# GyroBoard.net
KiCad netlist of a schematic drawn in Altium Designer
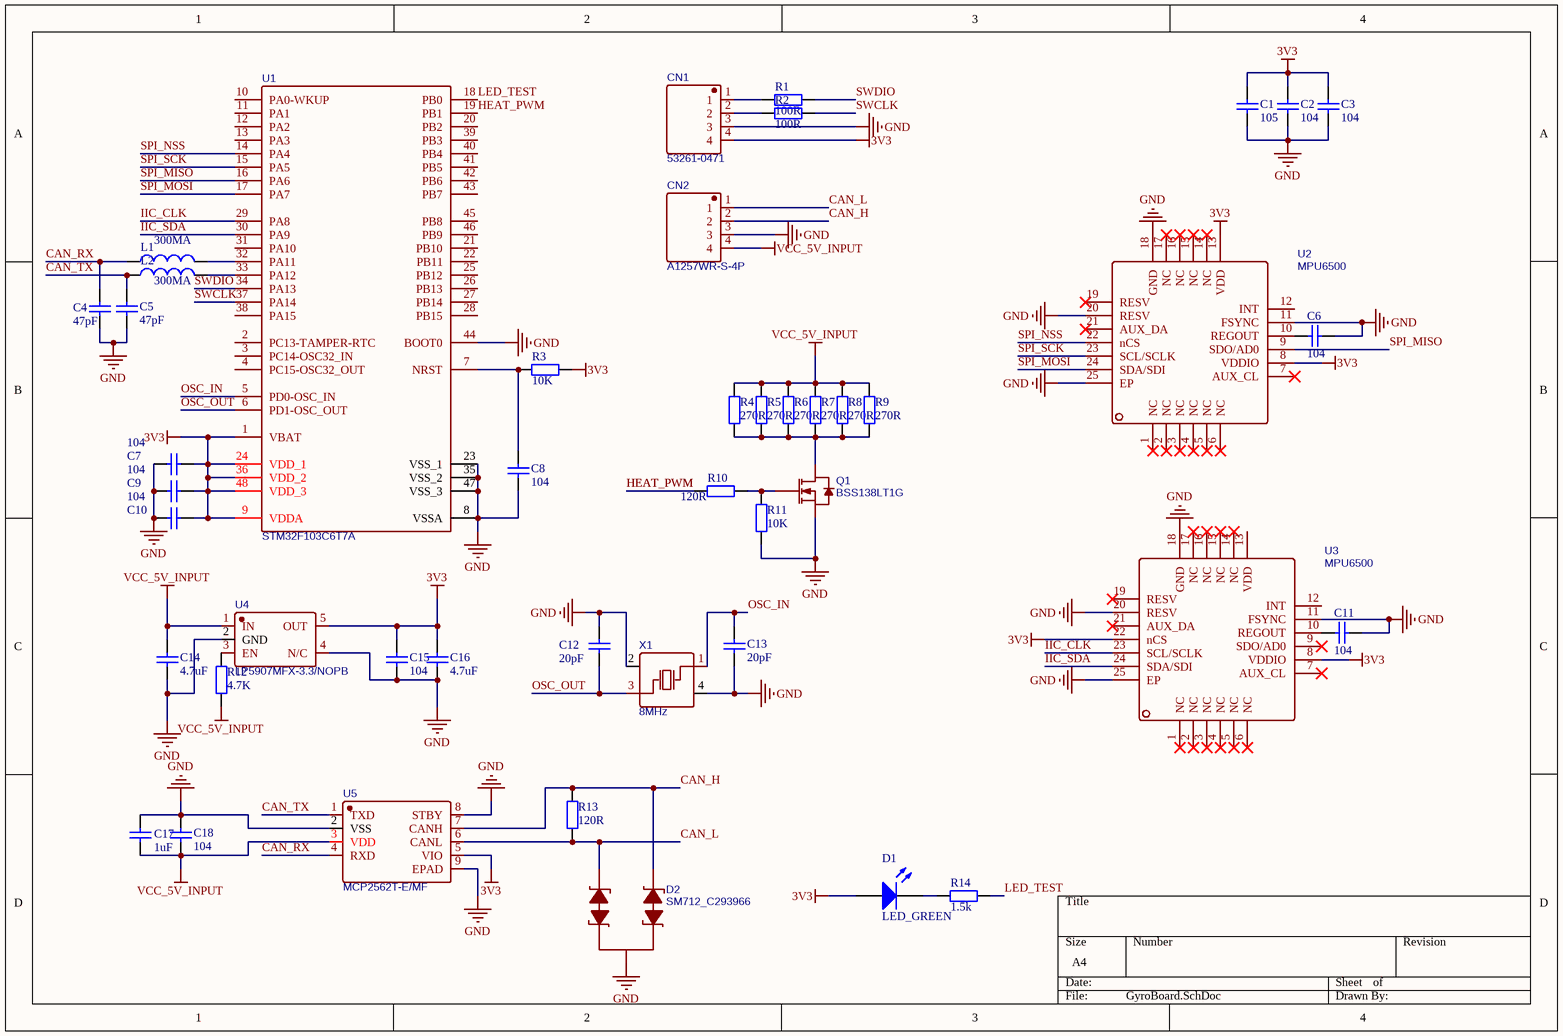
[diagram p0: GyroBoard.SchDoc]

(export (version "E")
  (design (tool "Eeschema 10.0.6"))
  (components
    (comp (ref "C1")
      (value "105")
      (footprint "0402")
      (description "Capacitor")
      (fields (field (name "PUBLISHER") "Altium Limited"))
      (libsource (lib "STM32 3.0") (part "Cap"))
    )
    (comp (ref "C2")
      (value "104")
      (footprint "0402")
      (description "Capacitor")
      (fields (field (name "PUBLISHER") "Altium Limited"))
      (libsource (lib "STM32 3.0") (part "Cap"))
    )
    (comp (ref "C3")
      (value "104")
      (footprint "0402")
      (description "Capacitor")
      (fields (field (name "PUBLISHER") "Altium Limited"))
      (libsource (lib "STM32 3.0") (part "Cap"))
    )
    (comp (ref "C4")
      (value "47pF")
      (footprint "0402")
      (description "Capacitor")
      (fields (field (name "PUBLISHER") "Altium Limited"))
      (libsource (lib "STM32 3.0") (part "Cap"))
    )
    (comp (ref "C5")
      (value "47pF")
      (footprint "0402")
      (description "Capacitor")
      (fields (field (name "PUBLISHER") "Altium Limited"))
      (libsource (lib "STM32 3.0") (part "Cap"))
    )
    (comp (ref "C6")
      (value "104")
      (footprint "0402")
      (description "Capacitor")
      (fields (field (name "PUBLISHER") "Altium Limited"))
      (libsource (lib "STM32 3.0") (part "Cap"))
    )
    (comp (ref "C7")
      (value "104")
      (footprint "0402")
      (description "Capacitor")
      (fields (field (name "PUBLISHER") "Altium Limited"))
      (libsource (lib "STM32 3.0") (part "Cap"))
    )
    (comp (ref "C8")
      (value "104")
      (footprint "0402")
      (description "Capacitor")
      (fields (field (name "PUBLISHER") "Altium Limited"))
      (libsource (lib "STM32 3.0") (part "Cap"))
    )
    (comp (ref "C9")
      (value "104")
      (footprint "0402")
      (description "Capacitor")
      (fields (field (name "PUBLISHER") "Altium Limited"))
      (libsource (lib "STM32 3.0") (part "Cap"))
    )
    (comp (ref "C10")
      (value "104")
      (footprint "0402")
      (description "Capacitor")
      (fields (field (name "PUBLISHER") "Altium Limited"))
      (libsource (lib "STM32 3.0") (part "Cap"))
    )
    (comp (ref "C11")
      (value "104")
      (footprint "0402")
      (description "Capacitor")
      (fields (field (name "PUBLISHER") "Altium Limited"))
      (libsource (lib "STM32 3.0") (part "Cap"))
    )
    (comp (ref "C12")
      (value "20pF")
      (footprint "0402")
      (description "Capacitor")
      (fields (field (name "PUBLISHER") "Altium Limited"))
      (libsource (lib "STM32 3.0") (part "Cap"))
    )
    (comp (ref "C13")
      (value "20pF")
      (footprint "0402")
      (description "Capacitor")
      (fields (field (name "PUBLISHER") "Altium Limited"))
      (libsource (lib "STM32 3.0") (part "Cap"))
    )
    (comp (ref "C14")
      (value "4.7uF")
      (footprint "0402")
      (description "Capacitor")
      (fields (field (name "PUBLISHER") "Altium Limited"))
      (libsource (lib "STM32 3.0") (part "Cap"))
    )
    (comp (ref "C15")
      (value "104")
      (footprint "0402")
      (description "Capacitor")
      (fields (field (name "PUBLISHER") "Altium Limited"))
      (libsource (lib "STM32 3.0") (part "Cap"))
    )
    (comp (ref "C16")
      (value "4.7uF")
      (footprint "CAP-CASE-A_3216")
      (description "Capacitor")
      (fields (field (name "PUBLISHER") "Altium Limited"))
      (libsource (lib "STM32 3.0") (part "Cap"))
    )
    (comp (ref "C17")
      (value "1uF")
      (footprint "0402")
      (description "Capacitor")
      (fields (field (name "PUBLISHER") "Altium Limited"))
      (libsource (lib "STM32 3.0") (part "Cap"))
    )
    (comp (ref "C18")
      (value "104")
      (footprint "0402")
      (description "Capacitor")
      (fields (field (name "PUBLISHER") "Altium Limited"))
      (libsource (lib "STM32 3.0") (part "Cap"))
    )
    (comp (ref "CN1")
      (value "53261-0471")
      (footprint "532610471")
      (fields
        (field (name "BOM_SUPPLIER PART") "C240848")
        (field (name "BOM_MANUFACTURER PART") "53261-0871")
        (field (name "CONTRIBUTOR") "LCSC")
      )
      (libsource (lib "GyroBoard") (part "53261-0471"))
    )
    (comp (ref "CN2")
      (value "A1257WR-S-4P")
      (footprint "A1257WR-S-4P")
      (fields
        (field (name "BOM_SUPPLIER PART") "C240848")
        (field (name "BOM_MANUFACTURER PART") "53261-0871")
        (field (name "CONTRIBUTOR") "LCSC")
      )
      (libsource (lib "GyroBoard") (part "A1257WV-S-4P"))
    )
    (comp (ref "D1")
      (value "LED_GREEN")
      (footprint "GyroBoard:LED-0603")
      (description "Typical INFRARED GaAs LED")
      (fields (field (name "PUBLISHER") "Altium Limited"))
      (libsource (lib "Miscellaneous Devices") (part "LED0"))
    )
    (comp (ref "D2")
      (value "SM712_C293966")
      (footprint "SOT-23-3")
      (fields
        (field (name "BOM_SUPPLIER PART") "C293966")
        (field (name "BOM_MANUFACTURER PART") "SM712")
        (field (name "CONTRIBUTOR") "LCSC")
      )
      (libsource (lib "GyroBoard") (part "SM712_C293966"))
    )
    (comp (ref "L1")
      (value "300MA")
      (footprint "GyroBoard:0402")
      (description "CBG100505U310T")
      (fields (field (name "PUBLISHER") "Altium Limited"))
      (libsource (lib "Miscellaneous Devices") (part "Inductor"))
    )
    (comp (ref "L2")
      (value "300MA")
      (footprint "GyroBoard:0402")
      (description "CBG100505U310T")
      (fields (field (name "PUBLISHER") "Altium Limited"))
      (libsource (lib "Miscellaneous Devices") (part "Inductor"))
    )
    (comp (ref "Q1")
      (value "BSS138LT1G")
      (footprint "SOT-23(SOT-23-3)")
      (fields (field (name "BOM_SUPPLIER PART") "C82045"))
      (libsource (lib "GyroBoard") (part "BSS138LT1G"))
    )
    (comp (ref "R1")
      (value "100R")
      (footprint "0402")
      (description "Resistor")
      (fields (field (name "PUBLISHER") "Altium Limited"))
      (libsource (lib "") (part "Res2_2"))
    )
    (comp (ref "R2")
      (value "100R")
      (footprint "0402")
      (description "Resistor")
      (fields (field (name "PUBLISHER") "Altium Limited"))
      (libsource (lib "") (part "Res2_2"))
    )
    (comp (ref "R3")
      (value "10K")
      (footprint "0402")
      (description "Resistor")
      (fields (field (name "PUBLISHER") "Altium Limited"))
      (libsource (lib "") (part "Res2_3"))
    )
    (comp (ref "R4")
      (value "270R")
      (footprint "0402")
      (description "Resistor")
      (fields (field (name "PUBLISHER") "Altium Limited"))
      (libsource (lib "") (part "Res2_1"))
    )
    (comp (ref "R5")
      (value "270R")
      (footprint "0402")
      (description "Resistor")
      (fields (field (name "PUBLISHER") "Altium Limited"))
      (libsource (lib "") (part "Res2_1"))
    )
    (comp (ref "R6")
      (value "270R")
      (footprint "0402")
      (description "Resistor")
      (fields (field (name "PUBLISHER") "Altium Limited"))
      (libsource (lib "") (part "Res2_1"))
    )
    (comp (ref "R7")
      (value "270R")
      (footprint "0402")
      (description "Resistor")
      (fields (field (name "PUBLISHER") "Altium Limited"))
      (libsource (lib "") (part "Res2_1"))
    )
    (comp (ref "R8")
      (value "270R")
      (footprint "0402")
      (description "Resistor")
      (fields (field (name "PUBLISHER") "Altium Limited"))
      (libsource (lib "") (part "Res2_1"))
    )
    (comp (ref "R9")
      (value "270R")
      (footprint "0402")
      (description "Resistor")
      (fields (field (name "PUBLISHER") "Altium Limited"))
      (libsource (lib "") (part "Res2_1"))
    )
    (comp (ref "R10")
      (value "120R")
      (footprint "0402")
      (description "Resistor")
      (fields (field (name "PUBLISHER") "Altium Limited"))
      (libsource (lib "") (part "Res2_2"))
    )
    (comp (ref "R11")
      (value "10K")
      (footprint "0402")
      (description "Resistor")
      (fields (field (name "PUBLISHER") "Altium Limited"))
      (libsource (lib "STM32 3.0") (part "Res2"))
    )
    (comp (ref "R12")
      (value "4.7K")
      (footprint "0402")
      (description "Resistor")
      (fields (field (name "PUBLISHER") "Altium Limited"))
      (libsource (lib "STM32 3.0") (part "Res2"))
    )
    (comp (ref "R13")
      (value "120R")
      (footprint "0402")
      (description "Resistor")
      (fields (field (name "PUBLISHER") "Altium Limited"))
      (libsource (lib "STM32 3.0") (part "Res2"))
    )
    (comp (ref "R14")
      (value "1.5k")
      (footprint "0402")
      (description "Resistor")
      (fields (field (name "PUBLISHER") "Altium Limited"))
      (libsource (lib "") (part "Res2_2"))
    )
    (comp (ref "U1")
      (value "STM32F103C6T7A")
      (footprint "QFP-48_LSA9.2-LSB9.2-H1.6-PITCH0.5-TL")
      (fields (field (name "BOM_SUPPLIER PART") "C222074") (field (name "CONTRIBUTOR") "LCSC"))
      (libsource (lib "GyroBoard") (part "STM32F103C6T7A"))
    )
    (comp (ref "U2")
      (value "MPU6500")
      (footprint "QFN24-EP")
      (fields (field (name "BOM_SUPPLIER PART") "C50278"))
      (libsource (lib "GyroBoard") (part "MPU6500_1"))
    )
    (comp (ref "U3")
      (value "MPU6500")
      (footprint "QFN24-EP")
      (fields (field (name "BOM_SUPPLIER PART") "C50278"))
      (libsource (lib "GyroBoard") (part "MPU6500_1"))
    )
    (comp (ref "U4")
      (value "LP5907MFX-3.3/NOPB")
      (footprint "SOT-23-5")
      (fields (field (name "BOM_SUPPLIER PART") "C80670") (field (name "CONTRIBUTOR") "LCSC"))
      (libsource (lib "GyroBoard") (part "LP5907MFX-3.3/NOPB"))
    )
    (comp (ref "U5")
      (value "MCP2562T-E/MF")
      (footprint "DFN-8_EP_3X3MM")
      (fields (field (name "BOM_SUPPLIER PART") "C191416") (field (name "CONTRIBUTOR") "LCSC"))
      (libsource (lib "GyroBoard") (part "MCP2562T-E/MF"))
    )
    (comp (ref "X1")
      (value "8MHz")
      (footprint "SMD-5032_4P")
      (fields
        (field (name "BOM_MANUFACTURER PART") "SMD-5032_4P8M20pf20ppm")
        (field (name "BOM_SUPPLIER PART") "C133333")
        (field (name "CONTRIBUTOR") "LCSC")
      )
      (libsource (lib "GyroBoard") (part "8MHz"))
    )
  )
  (nets
    (net (code "1") (name "/CAN_H") (class "Default")
      (node (ref "CN2") (pin "2") (pinfunction "2_2") (pintype "passive"))
      (node (ref "D2") (pin "1") (pinfunction "1_1") (pintype "passive"))
      (node (ref "R13") (pin "2") (pinfunction "2_2") (pintype "passive"))
      (node (ref "U5") (pin "7") (pinfunction "CANH_7") (pintype "passive"))
    )
    (net (code "2") (name "/CAN_L") (class "Default")
      (node (ref "CN2") (pin "1") (pinfunction "1_1") (pintype "passive"))
      (node (ref "D2") (pin "2") (pinfunction "2_2") (pintype "passive"))
      (node (ref "R13") (pin "1") (pinfunction "1_1") (pintype "passive"))
      (node (ref "U5") (pin "6") (pinfunction "CANL_6") (pintype "passive"))
    )
    (net (code "3") (name "/CAN_RX") (class "Default")
      (node (ref "C4") (pin "1") (pinfunction "1_1") (pintype "passive"))
      (node (ref "L1") (pin "1") (pinfunction "1_1") (pintype "passive"))
      (node (ref "U5") (pin "4") (pinfunction "RXD_4") (pintype "passive"))
    )
    (net (code "4") (name "/CAN_TX") (class "Default")
      (node (ref "C5") (pin "1") (pinfunction "1_1") (pintype "passive"))
      (node (ref "L2") (pin "1") (pinfunction "1_1") (pintype "passive"))
      (node (ref "U5") (pin "1") (pinfunction "TXD_1") (pintype "passive"))
    )
    (net (code "5") (name "/HEAT_PWM") (class "Default")
      (node (ref "R10") (pin "2") (pinfunction "2_2") (pintype "passive"))
      (node (ref "U1") (pin "19") (pinfunction "PB1_19") (pintype "passive"))
    )
    (net (code "6") (name "/IIC_CLK") (class "Default")
      (node (ref "U1") (pin "29") (pinfunction "PA8_29") (pintype "passive"))
      (node (ref "U3") (pin "23") (pinfunction "SCL/SCLK_23") (pintype "passive"))
    )
    (net (code "7") (name "/IIC_SDA") (class "Default")
      (node (ref "U1") (pin "30") (pinfunction "PA9_30") (pintype "passive"))
      (node (ref "U3") (pin "24") (pinfunction "SDA/SDI_24") (pintype "passive"))
    )
    (net (code "8") (name "/LED_TEST") (class "Default")
      (node (ref "R14") (pin "1") (pinfunction "1_1") (pintype "passive"))
      (node (ref "U1") (pin "18") (pinfunction "PB0_18") (pintype "passive"))
    )
    (net (code "9") (name "/OSC_IN") (class "Default")
      (node (ref "C13") (pin "1") (pinfunction "1_1") (pintype "passive"))
      (node (ref "U1") (pin "5") (pinfunction "PD0-OSC_IN_5") (pintype "passive"))
      (node (ref "X1") (pin "1") (pinfunction "OSC1_1") (pintype "passive"))
    )
    (net (code "10") (name "/OSC_OUT") (class "Default")
      (node (ref "C12") (pin "2") (pinfunction "2_2") (pintype "passive"))
      (node (ref "U1") (pin "6") (pinfunction "PD1-OSC_OUT_6") (pintype "passive"))
      (node (ref "X1") (pin "3") (pinfunction "OSC2_3") (pintype "passive"))
    )
    (net (code "11") (name "/SPI_MISO") (class "Default")
      (node (ref "U1") (pin "16") (pinfunction "PA6_16") (pintype "passive"))
      (node (ref "U2") (pin "9") (pinfunction "SDO/AD0_9") (pintype "passive"))
    )
    (net (code "12") (name "/SPI_MOSI") (class "Default")
      (node (ref "U1") (pin "17") (pinfunction "PA7_17") (pintype "passive"))
      (node (ref "U2") (pin "24") (pinfunction "SDA/SDI_24") (pintype "passive"))
    )
    (net (code "13") (name "/SPI_NSS") (class "Default")
      (node (ref "U1") (pin "14") (pinfunction "PA4_14") (pintype "passive"))
      (node (ref "U2") (pin "22") (pinfunction "nCS_22") (pintype "passive"))
    )
    (net (code "14") (name "/SPI_SCK") (class "Default")
      (node (ref "U1") (pin "15") (pinfunction "PA5_15") (pintype "passive"))
      (node (ref "U2") (pin "23") (pinfunction "SCL/SCLK_23") (pintype "passive"))
    )
    (net (code "15") (name "/SWCLK") (class "Default")
      (node (ref "R2") (pin "1") (pinfunction "1_1") (pintype "passive"))
      (node (ref "U1") (pin "37") (pinfunction "PA14_37") (pintype "passive"))
    )
    (net (code "16") (name "/SWDIO") (class "Default")
      (node (ref "R1") (pin "1") (pinfunction "1_1") (pintype "passive"))
      (node (ref "U1") (pin "34") (pinfunction "PA13_34") (pintype "passive"))
    )
    (net (code "17") (name "3V3") (class "Default")
      (node (ref "C1") (pin "2") (pinfunction "2_2") (pintype "passive"))
      (node (ref "C10") (pin "1") (pinfunction "1_1") (pintype "passive"))
      (node (ref "C15") (pin "2") (pinfunction "2_2") (pintype "passive"))
      (node (ref "C16") (pin "2") (pinfunction "2_2") (pintype "passive"))
      (node (ref "C2") (pin "2") (pinfunction "2_2") (pintype "passive"))
      (node (ref "C3") (pin "1") (pinfunction "1_1") (pintype "passive"))
      (node (ref "C7") (pin "1") (pinfunction "1_1") (pintype "passive"))
      (node (ref "C9") (pin "1") (pinfunction "1_1") (pintype "passive"))
      (node (ref "CN1") (pin "4") (pinfunction "4_4") (pintype "passive"))
      (node (ref "D1") (pin "1") (pinfunction "A_1") (pintype "passive"))
      (node (ref "R3") (pin "2") (pinfunction "2_2") (pintype "passive"))
      (node (ref "U1") (pin "1") (pinfunction "VBAT_1") (pintype "passive"))
      (node (ref "U1") (pin "24") (pinfunction "VDD_1_24") (pintype "passive"))
      (node (ref "U1") (pin "36") (pinfunction "VDD_2_36") (pintype "passive"))
      (node (ref "U1") (pin "48") (pinfunction "VDD_3_48") (pintype "passive"))
      (node (ref "U1") (pin "9") (pinfunction "VDDA_9") (pintype "passive"))
      (node (ref "U2") (pin "13") (pinfunction "VDD_13") (pintype "passive"))
      (node (ref "U2") (pin "8") (pinfunction "VDDIO_8") (pintype "passive"))
      (node (ref "U3") (pin "22") (pinfunction "nCS_22") (pintype "passive"))
      (node (ref "U3") (pin "8") (pinfunction "VDDIO_8") (pintype "passive"))
      (node (ref "U4") (pin "5") (pinfunction "OUT_5") (pintype "passive"))
      (node (ref "U5") (pin "5") (pinfunction "VIO_5") (pintype "passive"))
    )
    (net (code "18") (name "GND") (class "Default")
      (node (ref "C1") (pin "1") (pinfunction "1_1") (pintype "passive"))
      (node (ref "C10") (pin "2") (pinfunction "2_2") (pintype "passive"))
      (node (ref "C11") (pin "2") (pinfunction "2_2") (pintype "passive"))
      (node (ref "C12") (pin "1") (pinfunction "1_1") (pintype "passive"))
      (node (ref "C13") (pin "2") (pinfunction "2_2") (pintype "passive"))
      (node (ref "C14") (pin "2") (pinfunction "2_2") (pintype "passive"))
      (node (ref "C15") (pin "1") (pinfunction "1_1") (pintype "passive"))
      (node (ref "C16") (pin "1") (pinfunction "1_1") (pintype "passive"))
      (node (ref "C17") (pin "1") (pinfunction "1_1") (pintype "passive"))
      (node (ref "C18") (pin "1") (pinfunction "1_1") (pintype "passive"))
      (node (ref "C2") (pin "1") (pinfunction "1_1") (pintype "passive"))
      (node (ref "C3") (pin "2") (pinfunction "2_2") (pintype "passive"))
      (node (ref "C4") (pin "2") (pinfunction "2_2") (pintype "passive"))
      (node (ref "C5") (pin "2") (pinfunction "2_2") (pintype "passive"))
      (node (ref "C6") (pin "2") (pinfunction "2_2") (pintype "passive"))
      (node (ref "C7") (pin "2") (pinfunction "2_2") (pintype "passive"))
      (node (ref "C8") (pin "1") (pinfunction "1_1") (pintype "passive"))
      (node (ref "C9") (pin "2") (pinfunction "2_2") (pintype "passive"))
      (node (ref "CN1") (pin "3") (pinfunction "3_3") (pintype "passive"))
      (node (ref "CN2") (pin "3") (pinfunction "3_3") (pintype "passive"))
      (node (ref "D2") (pin "3") (pinfunction "3_3") (pintype "passive"))
      (node (ref "Q1") (pin "2") (pinfunction "S_2") (pintype "passive"))
      (node (ref "R11") (pin "1") (pinfunction "1_1") (pintype "passive"))
      (node (ref "U1") (pin "23") (pinfunction "VSS_1_23") (pintype "passive"))
      (node (ref "U1") (pin "35") (pinfunction "VSS_2_35") (pintype "passive"))
      (node (ref "U1") (pin "44") (pinfunction "BOOT0_44") (pintype "passive"))
      (node (ref "U1") (pin "47") (pinfunction "VSS_3_47") (pintype "passive"))
      (node (ref "U1") (pin "8") (pinfunction "VSSA_8") (pintype "passive"))
      (node (ref "U2") (pin "11") (pinfunction "FSYNC_11") (pintype "passive"))
      (node (ref "U2") (pin "18") (pinfunction "GND_18") (pintype "passive"))
      (node (ref "U2") (pin "20") (pinfunction "RESV_20") (pintype "passive"))
      (node (ref "U2") (pin "25") (pinfunction "EP_25") (pintype "passive"))
      (node (ref "U3") (pin "11") (pinfunction "FSYNC_11") (pintype "passive"))
      (node (ref "U3") (pin "18") (pinfunction "GND_18") (pintype "passive"))
      (node (ref "U3") (pin "20") (pinfunction "RESV_20") (pintype "passive"))
      (node (ref "U3") (pin "25") (pinfunction "EP_25") (pintype "passive"))
      (node (ref "U4") (pin "2") (pinfunction "GND_2") (pintype "passive"))
      (node (ref "U4") (pin "4") (pinfunction "N/C_4") (pintype "passive"))
      (node (ref "U5") (pin "2") (pinfunction "VSS_2") (pintype "passive"))
      (node (ref "U5") (pin "8") (pinfunction "STBY_8") (pintype "passive"))
      (node (ref "U5") (pin "9") (pinfunction "EPAD_9") (pintype "passive"))
      (node (ref "X1") (pin "2") (pinfunction "GND_2") (pintype "passive"))
      (node (ref "X1") (pin "4") (pinfunction "GND_4") (pintype "passive"))
    )
    (net (code "19") (name "Net-(CN1-Pad1)") (class "Default")
      (node (ref "CN1") (pin "1") (pinfunction "1_1") (pintype "passive"))
      (node (ref "R1") (pin "2") (pinfunction "2_2") (pintype "passive"))
    )
    (net (code "20") (name "Net-(CN1-Pad2)") (class "Default")
      (node (ref "CN1") (pin "2") (pinfunction "2_2") (pintype "passive"))
      (node (ref "R2") (pin "2") (pinfunction "2_2") (pintype "passive"))
    )
    (net (code "21") (name "Net-(D1-K)") (class "Default")
      (node (ref "D1") (pin "2") (pinfunction "K_2") (pintype "passive"))
      (node (ref "R14") (pin "2") (pinfunction "2_2") (pintype "passive"))
    )
    (net (code "22") (name "Net-(Q1-D)") (class "Default")
      (node (ref "Q1") (pin "3") (pinfunction "D_3") (pintype "passive"))
      (node (ref "R4") (pin "2") (pinfunction "2_2") (pintype "passive"))
      (node (ref "R5") (pin "2") (pinfunction "2_2") (pintype "passive"))
      (node (ref "R6") (pin "2") (pinfunction "2_2") (pintype "passive"))
      (node (ref "R7") (pin "2") (pinfunction "2_2") (pintype "passive"))
      (node (ref "R8") (pin "2") (pinfunction "2_2") (pintype "passive"))
      (node (ref "R9") (pin "2") (pinfunction "2_2") (pintype "passive"))
    )
    (net (code "23") (name "Net-(Q1-G)") (class "Default")
      (node (ref "Q1") (pin "1") (pinfunction "G_1") (pintype "passive"))
      (node (ref "R10") (pin "1") (pinfunction "1_1") (pintype "passive"))
      (node (ref "R11") (pin "2") (pinfunction "2_2") (pintype "passive"))
    )
    (net (code "24") (name "Net-(U1-NRST)") (class "Default")
      (node (ref "C8") (pin "2") (pinfunction "2_2") (pintype "passive"))
      (node (ref "R3") (pin "1") (pinfunction "1_1") (pintype "passive"))
      (node (ref "U1") (pin "7") (pinfunction "NRST_7") (pintype "passive"))
    )
    (net (code "25") (name "Net-(U1-PA11)") (class "Default")
      (node (ref "L1") (pin "2") (pinfunction "2_2") (pintype "passive"))
      (node (ref "U1") (pin "32") (pinfunction "PA11_32") (pintype "passive"))
    )
    (net (code "26") (name "Net-(U1-PA12)") (class "Default")
      (node (ref "L2") (pin "2") (pinfunction "2_2") (pintype "passive"))
      (node (ref "U1") (pin "33") (pinfunction "PA12_33") (pintype "passive"))
    )
    (net (code "27") (name "Net-(U2-REGOUT)") (class "Default")
      (node (ref "C6") (pin "1") (pinfunction "1_1") (pintype "passive"))
      (node (ref "U2") (pin "10") (pinfunction "REGOUT_10") (pintype "passive"))
    )
    (net (code "28") (name "Net-(U3-REGOUT)") (class "Default")
      (node (ref "C11") (pin "1") (pinfunction "1_1") (pintype "passive"))
      (node (ref "U3") (pin "10") (pinfunction "REGOUT_10") (pintype "passive"))
    )
    (net (code "29") (name "Net-(U4-EN)") (class "Default")
      (node (ref "R12") (pin "2") (pinfunction "2_2") (pintype "passive"))
      (node (ref "U4") (pin "3") (pinfunction "EN_3") (pintype "passive"))
    )
    (net (code "30") (name "VCC_5V_INPUT") (class "Default")
      (node (ref "C14") (pin "1") (pinfunction "1_1") (pintype "passive"))
      (node (ref "C17") (pin "2") (pinfunction "2_2") (pintype "passive"))
      (node (ref "C18") (pin "2") (pinfunction "2_2") (pintype "passive"))
      (node (ref "CN2") (pin "4") (pinfunction "4_4") (pintype "passive"))
      (node (ref "R12") (pin "1") (pinfunction "1_1") (pintype "passive"))
      (node (ref "R4") (pin "1") (pinfunction "1_1") (pintype "passive"))
      (node (ref "R5") (pin "1") (pinfunction "1_1") (pintype "passive"))
      (node (ref "R6") (pin "1") (pinfunction "1_1") (pintype "passive"))
      (node (ref "R7") (pin "1") (pinfunction "1_1") (pintype "passive"))
      (node (ref "R8") (pin "1") (pinfunction "1_1") (pintype "passive"))
      (node (ref "R9") (pin "1") (pinfunction "1_1") (pintype "passive"))
      (node (ref "U4") (pin "1") (pinfunction "IN_1") (pintype "passive"))
      (node (ref "U5") (pin "3") (pinfunction "VDD_3") (pintype "passive"))
    )
    (net (code "31") (name "unconnected-(U1-PA0-WKUP-Pad10)") (class "Default")
      (node (ref "U1") (pin "10") (pinfunction "PA0-WKUP_10") (pintype "passive"))
    )
    (net (code "32") (name "unconnected-(U1-PA1-Pad11)") (class "Default")
      (node (ref "U1") (pin "11") (pinfunction "PA1_11") (pintype "passive"))
    )
    (net (code "33") (name "unconnected-(U1-PA2-Pad12)") (class "Default")
      (node (ref "U1") (pin "12") (pinfunction "PA2_12") (pintype "passive"))
    )
    (net (code "34") (name "unconnected-(U1-PA3-Pad13)") (class "Default")
      (node (ref "U1") (pin "13") (pinfunction "PA3_13") (pintype "passive"))
    )
    (net (code "35") (name "unconnected-(U1-PA10-Pad31)") (class "Default")
      (node (ref "U1") (pin "31") (pinfunction "PA10_31") (pintype "passive"))
    )
    (net (code "36") (name "unconnected-(U1-PA15-Pad38)") (class "Default")
      (node (ref "U1") (pin "38") (pinfunction "PA15_38") (pintype "passive"))
    )
    (net (code "37") (name "unconnected-(U1-PB2-Pad20)") (class "Default")
      (node (ref "U1") (pin "20") (pinfunction "PB2_20") (pintype "passive"))
    )
    (net (code "38") (name "unconnected-(U1-PB3-Pad39)") (class "Default")
      (node (ref "U1") (pin "39") (pinfunction "PB3_39") (pintype "passive"))
    )
    (net (code "39") (name "unconnected-(U1-PB4-Pad40)") (class "Default")
      (node (ref "U1") (pin "40") (pinfunction "PB4_40") (pintype "passive"))
    )
    (net (code "40") (name "unconnected-(U1-PB5-Pad41)") (class "Default")
      (node (ref "U1") (pin "41") (pinfunction "PB5_41") (pintype "passive"))
    )
    (net (code "41") (name "unconnected-(U1-PB6-Pad42)") (class "Default")
      (node (ref "U1") (pin "42") (pinfunction "PB6_42") (pintype "passive"))
    )
    (net (code "42") (name "unconnected-(U1-PB7-Pad43)") (class "Default")
      (node (ref "U1") (pin "43") (pinfunction "PB7_43") (pintype "passive"))
    )
    (net (code "43") (name "unconnected-(U1-PB8-Pad45)") (class "Default")
      (node (ref "U1") (pin "45") (pinfunction "PB8_45") (pintype "passive"))
    )
    (net (code "44") (name "unconnected-(U1-PB9-Pad46)") (class "Default")
      (node (ref "U1") (pin "46") (pinfunction "PB9_46") (pintype "passive"))
    )
    (net (code "45") (name "unconnected-(U1-PB10-Pad21)") (class "Default")
      (node (ref "U1") (pin "21") (pinfunction "PB10_21") (pintype "passive"))
    )
    (net (code "46") (name "unconnected-(U1-PB11-Pad22)") (class "Default")
      (node (ref "U1") (pin "22") (pinfunction "PB11_22") (pintype "passive"))
    )
    (net (code "47") (name "unconnected-(U1-PB12-Pad25)") (class "Default")
      (node (ref "U1") (pin "25") (pinfunction "PB12_25") (pintype "passive"))
    )
    (net (code "48") (name "unconnected-(U1-PB13-Pad26)") (class "Default")
      (node (ref "U1") (pin "26") (pinfunction "PB13_26") (pintype "passive"))
    )
    (net (code "49") (name "unconnected-(U1-PB14-Pad27)") (class "Default")
      (node (ref "U1") (pin "27") (pinfunction "PB14_27") (pintype "passive"))
    )
    (net (code "50") (name "unconnected-(U1-PB15-Pad28)") (class "Default")
      (node (ref "U1") (pin "28") (pinfunction "PB15_28") (pintype "passive"))
    )
    (net (code "51") (name "unconnected-(U1-PC13-TAMPER-RTC-Pad2)") (class "Default")
      (node (ref "U1") (pin "2") (pinfunction "PC13-TAMPER-RTC_2") (pintype "passive"))
    )
    (net (code "52") (name "unconnected-(U1-PC14-OSC32_IN-Pad3)") (class "Default")
      (node (ref "U1") (pin "3") (pinfunction "PC14-OSC32_IN_3") (pintype "passive"))
    )
    (net (code "53") (name "unconnected-(U1-PC15-OSC32_OUT-Pad4)") (class "Default")
      (node (ref "U1") (pin "4") (pinfunction "PC15-OSC32_OUT_4") (pintype "passive"))
    )
    (net (code "54") (name "unconnected-(U2-AUX_CL-Pad7)") (class "Default")
      (node (ref "U2") (pin "7") (pinfunction "AUX_CL_7") (pintype "passive+no_connect"))
    )
    (net (code "55") (name "unconnected-(U2-AUX_DA-Pad21)") (class "Default")
      (node (ref "U2") (pin "21") (pinfunction "AUX_DA_21") (pintype "passive+no_connect"))
    )
    (net (code "56") (name "unconnected-(U2-INT-Pad12)") (class "Default")
      (node (ref "U2") (pin "12") (pinfunction "INT_12") (pintype "passive"))
    )
    (net (code "57") (name "unconnected-(U2-NC-Pad1)") (class "Default")
      (node (ref "U2") (pin "1") (pinfunction "NC_1") (pintype "passive+no_connect"))
    )
    (net (code "58") (name "unconnected-(U2-NC-Pad2)") (class "Default")
      (node (ref "U2") (pin "2") (pinfunction "NC_2") (pintype "passive+no_connect"))
    )
    (net (code "59") (name "unconnected-(U2-NC-Pad3)") (class "Default")
      (node (ref "U2") (pin "3") (pinfunction "NC_3") (pintype "passive+no_connect"))
    )
    (net (code "60") (name "unconnected-(U2-NC-Pad4)") (class "Default")
      (node (ref "U2") (pin "4") (pinfunction "NC_4") (pintype "passive+no_connect"))
    )
    (net (code "61") (name "unconnected-(U2-NC-Pad5)") (class "Default")
      (node (ref "U2") (pin "5") (pinfunction "NC_5") (pintype "passive+no_connect"))
    )
    (net (code "62") (name "unconnected-(U2-NC-Pad6)") (class "Default")
      (node (ref "U2") (pin "6") (pinfunction "NC_6") (pintype "passive+no_connect"))
    )
    (net (code "63") (name "unconnected-(U2-NC-Pad14)") (class "Default")
      (node (ref "U2") (pin "14") (pinfunction "NC_14") (pintype "passive+no_connect"))
    )
    (net (code "64") (name "unconnected-(U2-NC-Pad15)") (class "Default")
      (node (ref "U2") (pin "15") (pinfunction "NC_15") (pintype "passive+no_connect"))
    )
    (net (code "65") (name "unconnected-(U2-NC-Pad16)") (class "Default")
      (node (ref "U2") (pin "16") (pinfunction "NC_16") (pintype "passive+no_connect"))
    )
    (net (code "66") (name "unconnected-(U2-NC-Pad17)") (class "Default")
      (node (ref "U2") (pin "17") (pinfunction "NC_17") (pintype "passive+no_connect"))
    )
    (net (code "67") (name "unconnected-(U2-RESV-Pad19)") (class "Default")
      (node (ref "U2") (pin "19") (pinfunction "RESV_19") (pintype "passive+no_connect"))
    )
    (net (code "68") (name "unconnected-(U3-AUX_CL-Pad7)") (class "Default")
      (node (ref "U3") (pin "7") (pinfunction "AUX_CL_7") (pintype "passive+no_connect"))
    )
    (net (code "69") (name "unconnected-(U3-AUX_DA-Pad21)") (class "Default")
      (node (ref "U3") (pin "21") (pinfunction "AUX_DA_21") (pintype "passive+no_connect"))
    )
    (net (code "70") (name "unconnected-(U3-INT-Pad12)") (class "Default")
      (node (ref "U3") (pin "12") (pinfunction "INT_12") (pintype "passive"))
    )
    (net (code "71") (name "unconnected-(U3-NC-Pad1)") (class "Default")
      (node (ref "U3") (pin "1") (pinfunction "NC_1") (pintype "passive+no_connect"))
    )
    (net (code "72") (name "unconnected-(U3-NC-Pad2)") (class "Default")
      (node (ref "U3") (pin "2") (pinfunction "NC_2") (pintype "passive+no_connect"))
    )
    (net (code "73") (name "unconnected-(U3-NC-Pad3)") (class "Default")
      (node (ref "U3") (pin "3") (pinfunction "NC_3") (pintype "passive+no_connect"))
    )
    (net (code "74") (name "unconnected-(U3-NC-Pad4)") (class "Default")
      (node (ref "U3") (pin "4") (pinfunction "NC_4") (pintype "passive+no_connect"))
    )
    (net (code "75") (name "unconnected-(U3-NC-Pad5)") (class "Default")
      (node (ref "U3") (pin "5") (pinfunction "NC_5") (pintype "passive+no_connect"))
    )
    (net (code "76") (name "unconnected-(U3-NC-Pad6)") (class "Default")
      (node (ref "U3") (pin "6") (pinfunction "NC_6") (pintype "passive+no_connect"))
    )
    (net (code "77") (name "unconnected-(U3-NC-Pad14)") (class "Default")
      (node (ref "U3") (pin "14") (pinfunction "NC_14") (pintype "passive+no_connect"))
    )
    (net (code "78") (name "unconnected-(U3-NC-Pad15)") (class "Default")
      (node (ref "U3") (pin "15") (pinfunction "NC_15") (pintype "passive+no_connect"))
    )
    (net (code "79") (name "unconnected-(U3-NC-Pad16)") (class "Default")
      (node (ref "U3") (pin "16") (pinfunction "NC_16") (pintype "passive+no_connect"))
    )
    (net (code "80") (name "unconnected-(U3-NC-Pad17)") (class "Default")
      (node (ref "U3") (pin "17") (pinfunction "NC_17") (pintype "passive+no_connect"))
    )
    (net (code "81") (name "unconnected-(U3-RESV-Pad19)") (class "Default")
      (node (ref "U3") (pin "19") (pinfunction "RESV_19") (pintype "passive+no_connect"))
    )
    (net (code "82") (name "unconnected-(U3-SDO{slash}AD0-Pad9)") (class "Default")
      (node (ref "U3") (pin "9") (pinfunction "SDO/AD0_9") (pintype "passive+no_connect"))
    )
    (net (code "83") (name "unconnected-(U3-VDD-Pad13)") (class "Default")
      (node (ref "U3") (pin "13") (pinfunction "VDD_13") (pintype "passive"))
    )
  )
)
